# WCH-CH9160-R0-1v0.net
KiCad netlist of a schematic drawn in Altium Designer
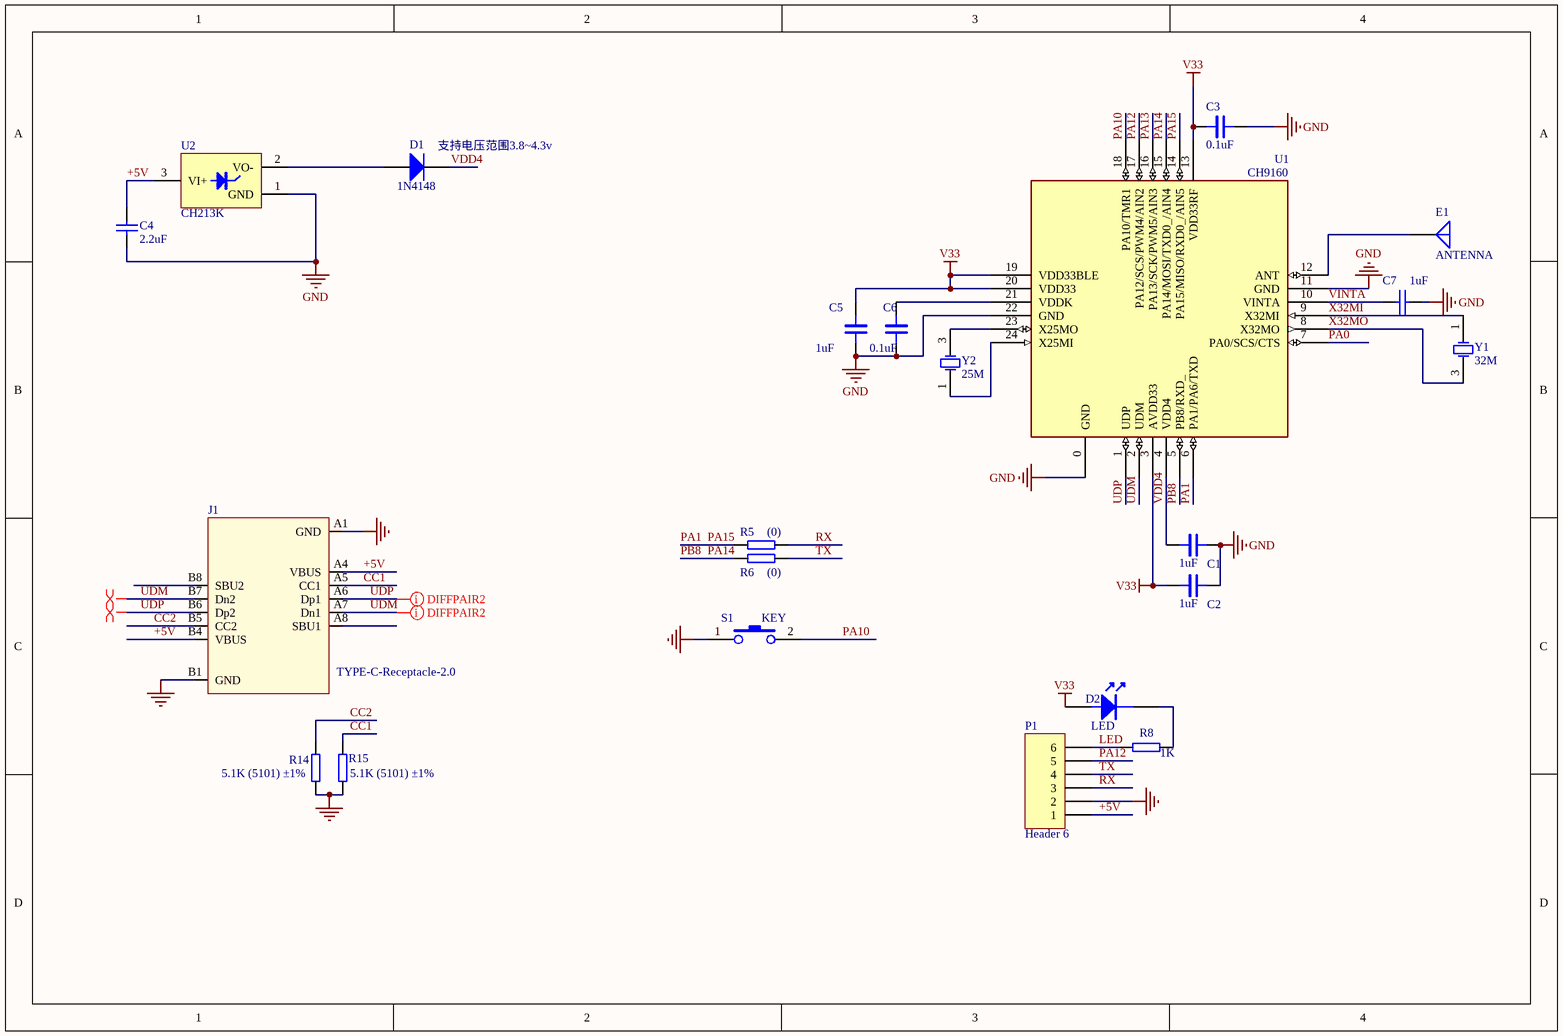
[diagram p0: WCH-CH9160-R0-1v0.SchDoc]

(export (version "E")
  (design (tool "Eeschema 10.0.6"))
  (components
    (comp (ref "C1")
      (value "1uF")
      (footprint "0603_C")
      (description "Capacitor")
      (libsource (lib "General") (part "CAP"))
    )
    (comp (ref "C2")
      (value "1uF")
      (footprint "0603_C")
      (description "Capacitor")
      (libsource (lib "General") (part "CAP"))
    )
    (comp (ref "C3")
      (value "0.1uF")
      (footprint "0603_C")
      (description "Capacitor")
      (libsource (lib "General") (part "CAP"))
    )
    (comp (ref "C4")
      (value "2.2uF")
      (footprint "0603_C")
      (description "Capacitor")
      (fields (field (name "PUBLISHER") "Altium Limited"))
      (libsource (lib "Miscellaneous Devices") (part "Cap"))
    )
    (comp (ref "C5")
      (value "1uF")
      (footprint "0603_C")
      (description "Capacitor")
      (libsource (lib "General") (part "CAP"))
    )
    (comp (ref "C6")
      (value "0.1uF")
      (footprint "0603_C")
      (description "Capacitor")
      (libsource (lib "General") (part "CAP"))
    )
    (comp (ref "C7")
      (value "1uF")
      (footprint "0603_C")
      (libsource (lib "BETOP Integrated_Library") (part "C0402"))
    )
    (comp (ref "D1")
      (value "1N4148")
      (footprint "1206+")
      (description "Default Diode")
      (fields (field (name "PUBLISHER") "Altium Limited"))
      (libsource (lib "Miscellaneous Devices") (part "Diode"))
    )
    (comp (ref "D2") (value "LED") (footprint "0603+") (libsource (lib "*") (part "LED")))
    (comp (ref "E1")
      (value "ANTENNA")
      (footprint "ANT-F-1-2.4G-1.6mmFR4")
      (description "Generic Antenna")
      (libsource (lib "*") (part "ANTENNA"))
    )
    (comp (ref "J1")
      (value "TYPE-C-Receptacle-2.0")
      (footprint "TYPE-C-Receptacle-2.0")
      (description "Type-C USB2.0 母座")
      (libsource (lib "Miscellaneous SCH Lib") (part "TYPE-C-Receptacle-2.0"))
    )
    (comp (ref "P1")
      (value "Header 6")
      (footprint "SIP6-2.54mm")
      (description "Header, 6-Pin")
      (fields (field (name "PUBLISHER") "Altium Limited"))
      (libsource (lib "Miscellaneous Connectors") (part "Header 6"))
    )
    (comp (ref "R5") (value "(0)") (footprint "0603") (libsource (lib "wch_sch_others") (part "RES")))
    (comp (ref "R6") (value "(0)") (footprint "0603") (libsource (lib "wch_sch_others") (part "RES")))
    (comp (ref "R8") (value "1K") (footprint "0603") (libsource (lib "wch_sch_others") (part "RES")))
    (comp (ref "R14")
      (value "5.1K (5101) ±1%")
      (footprint "0603")
      (libsource (lib "wch_sch_others") (part "RES"))
    )
    (comp (ref "R15")
      (value "5.1K (5101) ±1%")
      (footprint "0603")
      (libsource (lib "wch_sch_others") (part "RES"))
    )
    (comp (ref "S1")
      (value "KEY")
      (footprint "SMD_6.1x3.65x2.5mm-KEY")
      (libsource (lib "wch_sch_others") (part "KEY1"))
    )
    (comp (ref "U1")
      (value "CH9160")
      (footprint "QFN24_4X4")
      (description "BLE to USB2.0 high speed HID")
      (libsource (lib "DHXXXSCH") (part "CH9160"))
    )
    (comp (ref "U2")
      (value "CH213K")
      (footprint "SOT-23-3")
      (description "Ideal Diode 5V*1A")
      (libsource (lib "DHXXXSCH") (part "CH213K"))
    )
    (comp (ref "Y1")
      (value "32M")
      (footprint "XT3225")
      (description "Crystal Oscillator")
      (fields (field (name "PUBLISHER") "Altium Limited"))
      (libsource (lib "*") (part "XTAL"))
    )
    (comp (ref "Y2")
      (value "25M")
      (footprint "XT3225")
      (description "Crystal Oscillator")
      (fields (field (name "PUBLISHER") "Altium Limited"))
      (libsource (lib "*") (part "XTAL"))
    )
  )
  (nets
    (net (code "1") (name "/+5V") (class "Default")
      (node (ref "C4") (pin "2") (pinfunction "2_2") (pintype "passive"))
      (node (ref "J1") (pin "A4") (pinfunction "VBUS_A4") (pintype "passive"))
      (node (ref "J1") (pin "B4") (pinfunction "VBUS_B4") (pintype "passive"))
      (node (ref "P1") (pin "1") (pinfunction "1_1") (pintype "passive"))
      (node (ref "U2") (pin "3") (pinfunction "VI+_3") (pintype "power_in"))
    )
    (net (code "2") (name "/CC1") (class "Default")
      (node (ref "J1") (pin "A5") (pinfunction "CC1_A5") (pintype "passive"))
      (node (ref "R15") (pin "1") (pintype "passive"))
    )
    (net (code "3") (name "/CC2") (class "Default")
      (node (ref "J1") (pin "B5") (pinfunction "CC2_B5") (pintype "passive"))
      (node (ref "R14") (pin "1") (pintype "passive"))
    )
    (net (code "4") (name "/LED") (class "Default")
      (node (ref "P1") (pin "6") (pinfunction "6_6") (pintype "passive"))
      (node (ref "R8") (pin "1") (pintype "passive"))
    )
    (net (code "5") (name "/PA0") (class "Default")
      (node (ref "U1") (pin "7") (pinfunction "PA0/SCS/CTS_7") (pintype "bidirectional"))
    )
    (net (code "6") (name "/PA1") (class "Default")
      (node (ref "R5") (pin "1") (pintype "passive"))
      (node (ref "U1") (pin "14") (pinfunction "PA15/MISO/RXD0_/AIN5_14") (pintype "bidirectional"))
      (node (ref "U1") (pin "6") (pinfunction "PA1/PA6/TXD_6") (pintype "bidirectional"))
    )
    (net (code "7") (name "/PA10") (class "Default")
      (node (ref "S1") (pin "2") (pinfunction "2_2") (pintype "passive"))
      (node (ref "U1") (pin "18") (pinfunction "PA10/TMR1_18") (pintype "bidirectional"))
    )
    (net (code "8") (name "/PA12") (class "Default")
      (node (ref "P1") (pin "5") (pinfunction "5_5") (pintype "passive"))
      (node (ref "U1") (pin "17") (pinfunction "PA12/SCS/PWM4/AIN2_17") (pintype "bidirectional"))
    )
    (net (code "9") (name "/PA13") (class "Default")
      (node (ref "U1") (pin "16") (pinfunction "PA13/SCK/PWM5/AIN3_16") (pintype "bidirectional"))
    )
    (net (code "10") (name "/PA14") (class "Default")
      (node (ref "R6") (pin "1") (pintype "passive"))
      (node (ref "U1") (pin "15") (pinfunction "PA14/MOSI/TXD0_/AIN4_15") (pintype "bidirectional"))
      (node (ref "U1") (pin "5") (pinfunction "PB8/RXD__5") (pintype "bidirectional"))
    )
    (net (code "11") (name "/RX") (class "Default")
      (node (ref "P1") (pin "3") (pinfunction "3_3") (pintype "passive"))
      (node (ref "R5") (pin "2") (pintype "passive"))
    )
    (net (code "12") (name "/TX") (class "Default")
      (node (ref "P1") (pin "4") (pinfunction "4_4") (pintype "passive"))
      (node (ref "R6") (pin "2") (pintype "passive"))
    )
    (net (code "13") (name "/UDM") (class "Default")
      (node (ref "J1") (pin "A7") (pinfunction "Dn1_A7") (pintype "passive"))
      (node (ref "J1") (pin "B7") (pinfunction "Dn2_B7") (pintype "passive"))
      (node (ref "U1") (pin "2") (pinfunction "UDM_2") (pintype "bidirectional"))
    )
    (net (code "14") (name "/UDP") (class "Default")
      (node (ref "J1") (pin "A6") (pinfunction "Dp1_A6") (pintype "passive"))
      (node (ref "J1") (pin "B6") (pinfunction "Dp2_B6") (pintype "passive"))
      (node (ref "U1") (pin "1") (pinfunction "UDP_1") (pintype "bidirectional"))
    )
    (net (code "15") (name "/VDD4") (class "Default")
      (node (ref "C1") (pin "2") (pinfunction "2_2") (pintype "passive"))
      (node (ref "D1") (pin "2") (pinfunction "K_2") (pintype "passive"))
      (node (ref "U1") (pin "4") (pinfunction "VDD4_4") (pintype "power_in"))
    )
    (net (code "16") (name "/VINTA") (class "Default")
      (node (ref "C7") (pin "2") (pintype "passive"))
      (node (ref "U1") (pin "10") (pinfunction "VINTA_10") (pintype "power_in"))
    )
    (net (code "17") (name "/X32MI") (class "Default")
      (node (ref "U1") (pin "9") (pinfunction "X32MI_9") (pintype "input"))
      (node (ref "Y1") (pin "1") (pinfunction "OSC1_1") (pintype "passive"))
    )
    (net (code "18") (name "/X32MO") (class "Default")
      (node (ref "U1") (pin "8") (pinfunction "X32MO_8") (pintype "output"))
      (node (ref "Y1") (pin "3") (pinfunction "OSC2_3") (pintype "passive"))
    )
    (net (code "19") (name "GND") (class "Default")
      (node (ref "C1") (pin "1") (pinfunction "1_1") (pintype "passive"))
      (node (ref "C2") (pin "1") (pinfunction "1_1") (pintype "passive"))
      (node (ref "C3") (pin "2") (pinfunction "2_2") (pintype "passive"))
      (node (ref "C4") (pin "1") (pinfunction "1_1") (pintype "passive"))
      (node (ref "C5") (pin "2") (pinfunction "2_2") (pintype "passive"))
      (node (ref "C6") (pin "1") (pinfunction "1_1") (pintype "passive"))
      (node (ref "C7") (pin "1") (pintype "passive"))
      (node (ref "J1") (pin "A1") (pinfunction "GND_A1") (pintype "passive"))
      (node (ref "J1") (pin "B1") (pinfunction "GND_B1") (pintype "passive"))
      (node (ref "P1") (pin "2") (pinfunction "2_2") (pintype "passive"))
      (node (ref "R14") (pin "2") (pintype "passive"))
      (node (ref "R15") (pin "2") (pintype "passive"))
      (node (ref "S1") (pin "1") (pinfunction "1_1") (pintype "passive"))
      (node (ref "U1") (pin "0") (pinfunction "GND_0") (pintype "power_in"))
      (node (ref "U1") (pin "11") (pinfunction "GND_11") (pintype "power_in"))
      (node (ref "U1") (pin "22") (pinfunction "GND_22") (pintype "power_in"))
      (node (ref "U2") (pin "1") (pinfunction "GND_1") (pintype "power_in"))
    )
    (net (code "20") (name "Net-(D1-A)") (class "Default")
      (node (ref "D1") (pin "1") (pinfunction "A_1") (pintype "passive"))
      (node (ref "U2") (pin "2") (pinfunction "VO-_2") (pintype "power_in"))
    )
    (net (code "21") (name "Net-(D2-Pad2)") (class "Default")
      (node (ref "D2") (pin "2") (pinfunction "2_2") (pintype "passive"))
      (node (ref "R8") (pin "2") (pintype "passive"))
    )
    (net (code "22") (name "Net-(E1-A)") (class "Default")
      (node (ref "E1") (pin "1") (pinfunction "A_1") (pintype "passive"))
      (node (ref "U1") (pin "12") (pinfunction "ANT_12") (pintype "bidirectional"))
    )
    (net (code "23") (name "Net-(U1-VDDK)") (class "Default")
      (node (ref "C6") (pin "2") (pinfunction "2_2") (pintype "passive"))
      (node (ref "U1") (pin "21") (pinfunction "VDDK_21") (pintype "power_in"))
    )
    (net (code "24") (name "Net-(U1-X25MI)") (class "Default")
      (node (ref "U1") (pin "24") (pinfunction "X25MI_24") (pintype "input"))
      (node (ref "Y2") (pin "1") (pinfunction "OSC1_1") (pintype "passive"))
    )
    (net (code "25") (name "Net-(U1-X25MO)") (class "Default")
      (node (ref "U1") (pin "23") (pinfunction "X25MO_23") (pintype "bidirectional"))
      (node (ref "Y2") (pin "3") (pinfunction "OSC2_3") (pintype "passive"))
    )
    (net (code "26") (name "V33") (class "Default")
      (node (ref "C2") (pin "2") (pinfunction "2_2") (pintype "passive"))
      (node (ref "C3") (pin "1") (pinfunction "1_1") (pintype "passive"))
      (node (ref "C5") (pin "1") (pinfunction "1_1") (pintype "passive"))
      (node (ref "D2") (pin "1") (pinfunction "1_1") (pintype "passive"))
      (node (ref "U1") (pin "13") (pinfunction "VDD33RF_13") (pintype "power_in"))
      (node (ref "U1") (pin "19") (pinfunction "VDD33BLE_19") (pintype "power_in"))
      (node (ref "U1") (pin "20") (pinfunction "VDD33_20") (pintype "power_in"))
      (node (ref "U1") (pin "3") (pinfunction "AVDD33_3") (pintype "power_in"))
    )
    (net (code "27") (name "unconnected-(J1-SBU1-PadA8)") (class "Default")
      (node (ref "J1") (pin "A8") (pinfunction "SBU1_A8") (pintype "passive"))
    )
    (net (code "28") (name "unconnected-(J1-SBU2-PadB8)") (class "Default")
      (node (ref "J1") (pin "B8") (pinfunction "SBU2_B8") (pintype "passive"))
    )
  )
)
